# TSAL_REV1.net
KiCad netlist of a schematic drawn in Altium Designer
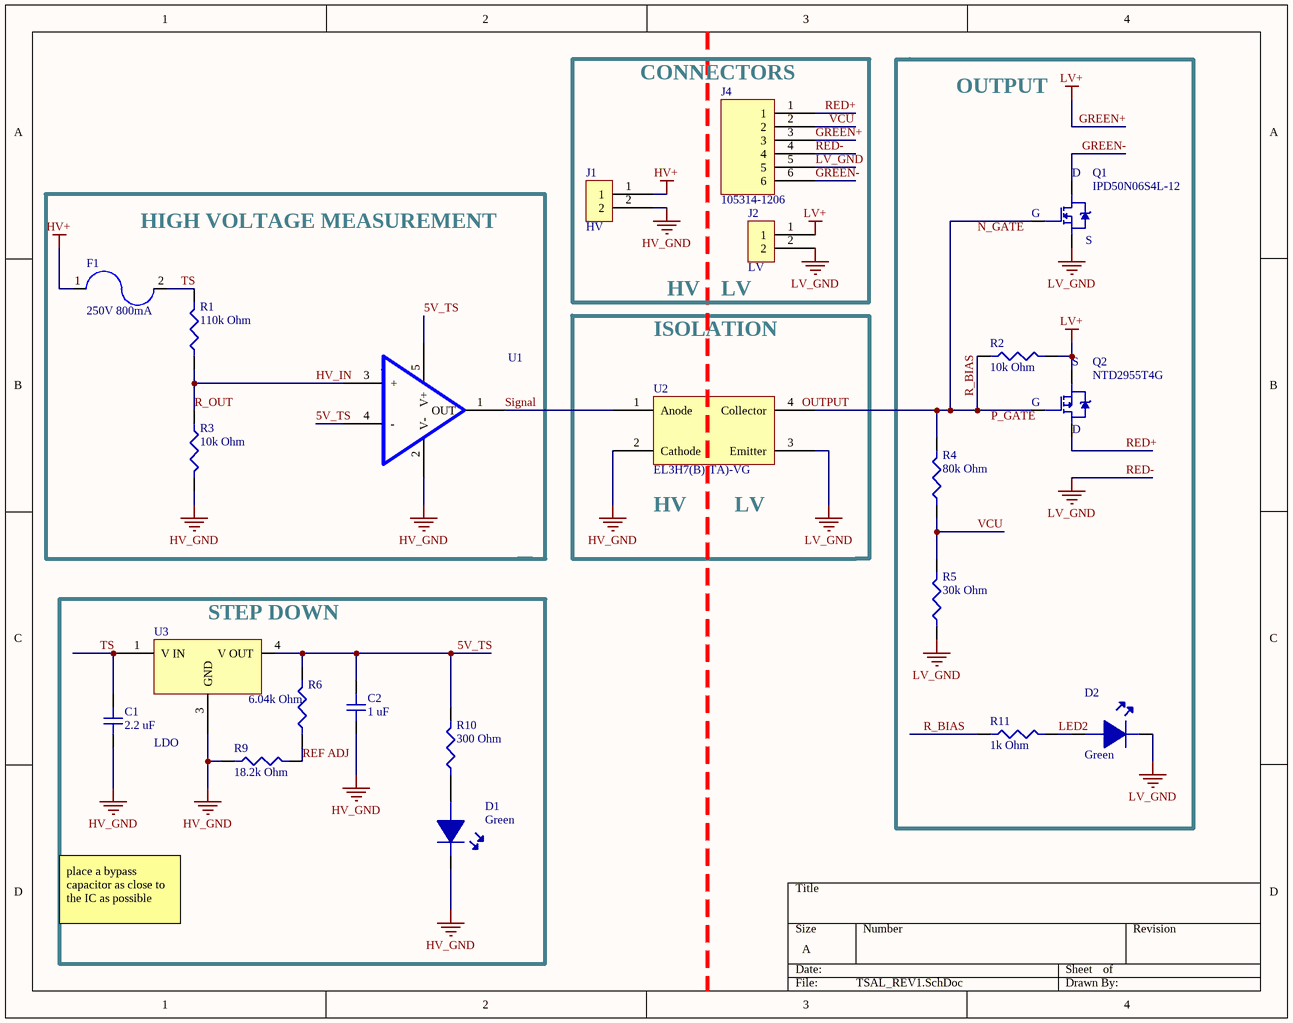
[diagram p0: TSAL_REV1.SchDoc]

(export (version "E")
  (design (tool "Eeschema 10.0.6"))
  (components
    (comp (ref "C1")
      (value "2.2 uF")
      (footprint "CAPC5850X25N")
      (description "CAP CER 2.2UF 250V X7T 2220")
      (fields
        (field (name "MANUFACTURER") "TDK")
        (field (name "MANUFACTURER PART NUMBER") "CGA9P3X7T2E225K250KE")
      )
      (libsource (lib "TSAL_REV1") (part "CGA9P3X7T2E225K250KE"))
    )
    (comp (ref "C2")
      (value "1 uF")
      (description "Cap Ceramic 1uF 10V X5R 10% SMD 0603 85C Paper T/R")
      (fields
        (field (name "MANUFACTURER") "Samsung")
        (field (name "MANUFACTURER PART NUMBER") "CL10A105KP8NNNC")
      )
      (libsource (lib "TSAL_REV1") (part "CL10A105KP8NNNC"))
    )
    (comp (ref "D1")
      (value "Green")
      (footprint "LED_0603")
      (description "LED Uni-Color Green 574nm 2-Pin Chip LED T/R")
      (fields
        (field (name "MANUFACTURER") "Vishay Lite-On")
        (field (name "MANUFACTURER PART NUMBER") "LTST-C191KGKT")
      )
      (libsource (lib "TSAL_REV1") (part "LTST-C191KGKT"))
    )
    (comp (ref "D2")
      (value "Green")
      (footprint "LED_0603")
      (description "LED Uni-Color Green 574nm 2-Pin Chip LED T/R")
      (fields
        (field (name "MANUFACTURER") "Vishay Lite-On")
        (field (name "MANUFACTURER PART NUMBER") "LTST-C191KGKT")
      )
      (libsource (lib "TSAL_REV1") (part "LTST-C191KGKT"))
    )
    (comp (ref "F1")
      (value "250V 800mA")
      (footprint "FUSE_SMD")
      (fields (field (name "MANUFACTURER") "Bel") (field (name "MANUFACTURER PART NUMBER") "0678D0800-02"))
      (libsource (lib "TSAL_REV1") (part "0678D0800-02"))
    )
    (comp (ref "J1")
      (value "HV")
      (footprint "2_PIN_CONNECTOR")
      (fields (field (name "MANUFACTURER") "Molex") (field (name "MANUFACTURER PART NUMBER") "0705530001"))
      (libsource (lib "TSAL_REV1") (part "0705530001"))
    )
    (comp (ref "J2")
      (value "LV")
      (footprint "2_PIN_CONNECTOR")
      (fields (field (name "MANUFACTURER") "Molex") (field (name "MANUFACTURER PART NUMBER") "0705530001"))
      (libsource (lib "TSAL_REV1") (part "0705530001"))
    )
    (comp (ref "J4")
      (value "105314-1206")
      (footprint "*MOLEX_1053141206")
      (description "CONN HEADER R/A 6POS 2.5MM")
      (fields (field (name "MANUFACTURER") "Molex"))
      (libsource (lib "TSAL_REV1") (part "105314-1206"))
    )
    (comp (ref "Q1")
      (value "IPD50N06S4L-12")
      (footprint "DPAK228P998X235-3N")
      (description "MOSFET N-CH 60V 50A TO252-3-11")
      (fields (field (name "MANUFACTURER") "Infineon"))
      (libsource (lib "TSAL_REV1") (part "IPD50N06S4L-12"))
    )
    (comp (ref "Q2")
      (value "NTD2955T4G")
      (footprint "DPAK228P991X238-3N")
      (description "Trans MOSFET P-CH 60V 12A 3-Pin(2+Tab) DPAK T/R")
      (fields (field (name "MANUFACTURER") "ON Semiconductor"))
      (libsource (lib "TSAL_REV1") (part "NTD2955T4G"))
    )
    (comp (ref "R1")
      (value "110k Ohm")
      (footprint "RESC3116X06N")
      (description "RES SMD 110K OHM 1% 1/4W 1206")
      (fields
        (field (name "MANUFACTURER") "Yageo")
        (field (name "MANUFACTURER PART NUMBER") "RC1206FR-07110KL")
      )
      (libsource (lib "TSAL_REV1") (part "RC1206FR-07110KL"))
    )
    (comp (ref "R2")
      (value "10k Ohm")
      (footprint "RESC2012X06N")
      (description "RES 10K OHM 1% 1/4W 0805")
      (fields
        (field (name "MANUFACTURER") "Stackpole Electronics")
        (field (name "MANUFACTURER PART NUMBER") "RNCP0805FTD10K0")
      )
      (libsource (lib "TSAL_REV1") (part "RNCP0805FTD10K0"))
    )
    (comp (ref "R3")
      (value "10k Ohm")
      (footprint "RESC2012X06N")
      (description "RES 10K OHM 1% 1/4W 0805")
      (fields
        (field (name "MANUFACTURER") "Stackpole Electronics")
        (field (name "MANUFACTURER PART NUMBER") "RNCP0805FTD10K0")
      )
      (libsource (lib "TSAL_REV1") (part "RNCP0805FTD10K0"))
    )
    (comp (ref "R4")
      (value "80k Ohm")
      (footprint "RESC1608X06N")
      (description "RES 80K OHM 0.1% 0.15W 0603")
      (fields
        (field (name "MANUFACTURER") "Vishay Dale")
        (field (name "MANUFACTURER PART NUMBER") "PTN0603E8002BST1")
      )
      (libsource (lib "TSAL_REV1") (part "PTN0603E8002BST1"))
    )
    (comp (ref "R5")
      (value "30k Ohm")
      (footprint "RESC2012X06N")
      (description "Thick Film Resistors CRG0805 1% 30K")
      (fields
        (field (name "MANUFACTURER") "TE Connectivity")
        (field (name "MANUFACTURER PART NUMBER") "CRG0805F30K")
      )
      (libsource (lib "TSAL_REV1") (part "CRG0805F30K"))
    )
    (comp (ref "R6")
      (value "6.04k Ohm")
      (footprint "RESC2012X06N")
      (description "RES SMD 6.04KOHM 0.5% 1/10W 0805")
      (fields
        (field (name "MANUFACTURER") "Susumu")
        (field (name "MANUFACTURER PART NUMBER") "RR1220P-6041-D-M")
      )
      (libsource (lib "TSAL_REV1") (part "RR1220P-6041-D-M"))
    )
    (comp (ref "R9")
      (value "18.2k Ohm")
      (footprint "RESC2012X06N")
      (description "Panasonic ERA Series Thin Film Surface Mount Resistor 0805 Case 18.2k 0.1% 0.125W 25ppm/C")
      (fields
        (field (name "MANUFACTURER") "Panasonic")
        (field (name "MANUFACTURER PART NUMBER") "ERA-6AEB1822V")
      )
      (libsource (lib "TSAL_REV1") (part "ERA-6AEB1822V"))
    )
    (comp (ref "R10")
      (value "300 Ohm")
      (footprint "RESC1608X06N")
      (description "RES SMD 300 OHM 0.5% 1/16W 0603")
      (fields
        (field (name "MANUFACTURER") "Susumu")
        (field (name "MANUFACTURER PART NUMBER") "RR0816P-301-D")
      )
      (libsource (lib "TSAL_REV1") (part "RR0816P-301-D"))
    )
    (comp (ref "R11")
      (value "1k Ohm")
      (footprint "RESC1608X06N")
      (description "RES SMD 1K OHM 5% 1/10W 0603")
      (fields
        (field (name "MANUFACTURER") "Yageo")
        (field (name "MANUFACTURER PART NUMBER") "RC0603JR-071KL")
      )
      (libsource (lib "TSAL_REV1") (part "RC0603JR-071KL"))
    )
    (comp (ref "U1")
      (value "TS861ILT")
      (footprint "SOT95P280X145-5N")
      (description "COMPARATOR, MICROPWR, P PULL, 5")
      (fields (field (name "MANUFACTURER") "STMicroelectronics"))
      (libsource (lib "TSAL_REV1") (part "TS861ILT"))
    )
    (comp (ref "U2")
      (value "EL3H7(B)(TA)-VG")
      (footprint "SOIC127P700X200-4N")
      (description "OPTOISOLATOR 3.75KV TRANS 4-SSOP")
      (fields (field (name "MANUFACTURER") "Everlight"))
      (libsource (lib "TSAL_REV1") (part "EL3H7(B)(TA)-VG"))
    )
    (comp (ref "U3")
      (value "LDO")
      (footprint "DPAK228P991X238-3N")
      (description "Standard Regulator Pos 1.2V to 440V 0.01A 3-Pin(2+Tab) TO-252")
      (fields (field (name "MANUFACTURER") "Microchip") (field (name "MANUFACTURER PART NUMBER") "LR8K4-G"))
      (libsource (lib "TSAL_REV1") (part "LR8K4-G"))
    )
  )
  (nets
    (net (code "1") (name "/5V_TS") (class "Default")
      (node (ref "C2") (pin "2") (pinfunction "2_2") (pintype "passive"))
      (node (ref "R10") (pin "2") (pinfunction "2_2") (pintype "passive"))
      (node (ref "R6") (pin "2") (pinfunction "2_2") (pintype "passive"))
      (node (ref "U1") (pin "4") (pinfunction "-_4") (pintype "passive"))
      (node (ref "U1") (pin "5") (pinfunction "V+_5") (pintype "passive"))
      (node (ref "U3") (pin "4") (pinfunction "V_OUT_4") (pintype "passive"))
    )
    (net (code "2") (name "/GREEN-") (class "Default")
      (node (ref "J4") (pin "6") (pinfunction "6_6") (pintype "passive"))
      (node (ref "Q1") (pin "4") (pinfunction "4_4") (pintype "passive"))
    )
    (net (code "3") (name "/HV_IN") (class "Default")
      (node (ref "R1") (pin "1") (pinfunction "1_1") (pintype "passive"))
      (node (ref "R3") (pin "1") (pinfunction "1_1") (pintype "passive"))
      (node (ref "U1") (pin "3") (pinfunction "+_3") (pintype "passive"))
    )
    (net (code "4") (name "/LED2") (class "Default")
      (node (ref "D2") (pin "1") (pinfunction "1_1") (pintype "passive"))
      (node (ref "R11") (pin "2") (pinfunction "2_2") (pintype "passive"))
    )
    (net (code "8") (name "/RED+") (class "Default")
      (node (ref "J4") (pin "1") (pinfunction "1_1") (pintype "passive"))
      (node (ref "Q2") (pin "3") (pinfunction "3_3") (pintype "passive"))
    )
    (net (code "9") (name "/REF ADJ") (class "Default")
      (node (ref "R6") (pin "1") (pinfunction "1_1") (pintype "passive"))
      (node (ref "R9") (pin "2") (pinfunction "2_2") (pintype "passive"))
    )
    (net (code "10") (name "/R_BIAS") (class "Default")
      (node (ref "Q1") (pin "1") (pinfunction "1_1") (pintype "passive"))
      (node (ref "Q2") (pin "1") (pinfunction "1_1") (pintype "passive"))
      (node (ref "R11") (pin "1") (pinfunction "1_1") (pintype "passive"))
      (node (ref "R2") (pin "1") (pinfunction "1_1") (pintype "passive"))
      (node (ref "R4") (pin "2") (pinfunction "2_2") (pintype "passive"))
      (node (ref "U2") (pin "4") (pinfunction "Collector_4") (pintype "passive"))
    )
    (net (code "11") (name "/Signal") (class "Default")
      (node (ref "U1") (pin "1") (pinfunction "OUT_1") (pintype "passive"))
      (node (ref "U2") (pin "1") (pinfunction "Anode_1") (pintype "passive"))
    )
    (net (code "12") (name "/TS") (class "Default")
      (node (ref "C1") (pin "2") (pinfunction "2_2") (pintype "passive"))
      (node (ref "F1") (pin "2") (pinfunction "2_2") (pintype "passive"))
      (node (ref "R1") (pin "2") (pinfunction "2_2") (pintype "passive"))
      (node (ref "U3") (pin "1") (pinfunction "V_IN_1") (pintype "passive"))
    )
    (net (code "13") (name "/VCU") (class "Default")
      (node (ref "J4") (pin "2") (pinfunction "2_2") (pintype "passive"))
      (node (ref "R4") (pin "1") (pinfunction "1_1") (pintype "passive"))
      (node (ref "R5") (pin "2") (pinfunction "2_2") (pintype "passive"))
    )
    (net (code "14") (name "HV+") (class "Default")
      (node (ref "F1") (pin "1") (pinfunction "1_1") (pintype "passive"))
      (node (ref "J1") (pin "1") (pinfunction "1_1") (pintype "passive"))
    )
    (net (code "15") (name "HV_GND") (class "Default")
      (node (ref "C1") (pin "1") (pinfunction "1_1") (pintype "passive"))
      (node (ref "C2") (pin "1") (pinfunction "1_1") (pintype "passive"))
      (node (ref "D1") (pin "2") (pinfunction "2_2") (pintype "passive"))
      (node (ref "J1") (pin "2") (pinfunction "2_2") (pintype "passive"))
      (node (ref "R3") (pin "2") (pinfunction "2_2") (pintype "passive"))
      (node (ref "R9") (pin "1") (pinfunction "1_1") (pintype "passive"))
      (node (ref "U1") (pin "2") (pinfunction "V-_2") (pintype "passive"))
      (node (ref "U2") (pin "2") (pinfunction "Cathode_2") (pintype "passive"))
      (node (ref "U3") (pin "3") (pinfunction "GND_3") (pintype "passive"))
    )
    (net (code "16") (name "LV+") (class "Default")
      (node (ref "J2") (pin "1") (pinfunction "1_1") (pintype "passive"))
      (node (ref "J4") (pin "3") (pinfunction "3_3") (pintype "passive"))
      (node (ref "Q2") (pin "4") (pinfunction "4_4") (pintype "passive"))
      (node (ref "R2") (pin "2") (pinfunction "2_2") (pintype "passive"))
    )
    (net (code "17") (name "LV_GND") (class "Default")
      (node (ref "D2") (pin "2") (pinfunction "2_2") (pintype "passive"))
      (node (ref "J2") (pin "2") (pinfunction "2_2") (pintype "passive"))
      (node (ref "J4") (pin "4") (pinfunction "4_4") (pintype "passive"))
      (node (ref "J4") (pin "5") (pinfunction "5_5") (pintype "passive"))
      (node (ref "Q1") (pin "3") (pinfunction "3_3") (pintype "passive"))
      (node (ref "R5") (pin "1") (pinfunction "1_1") (pintype "passive"))
      (node (ref "U2") (pin "3") (pinfunction "Emitter_3") (pintype "passive"))
    )
    (net (code "18") (name "Net-(D1-Pad1)") (class "Default")
      (node (ref "D1") (pin "1") (pinfunction "1_1") (pintype "passive"))
      (node (ref "R10") (pin "1") (pinfunction "1_1") (pintype "passive"))
    )
  )
)
